# signal-board.net
KiCad netlist of a schematic drawn in EAGLE
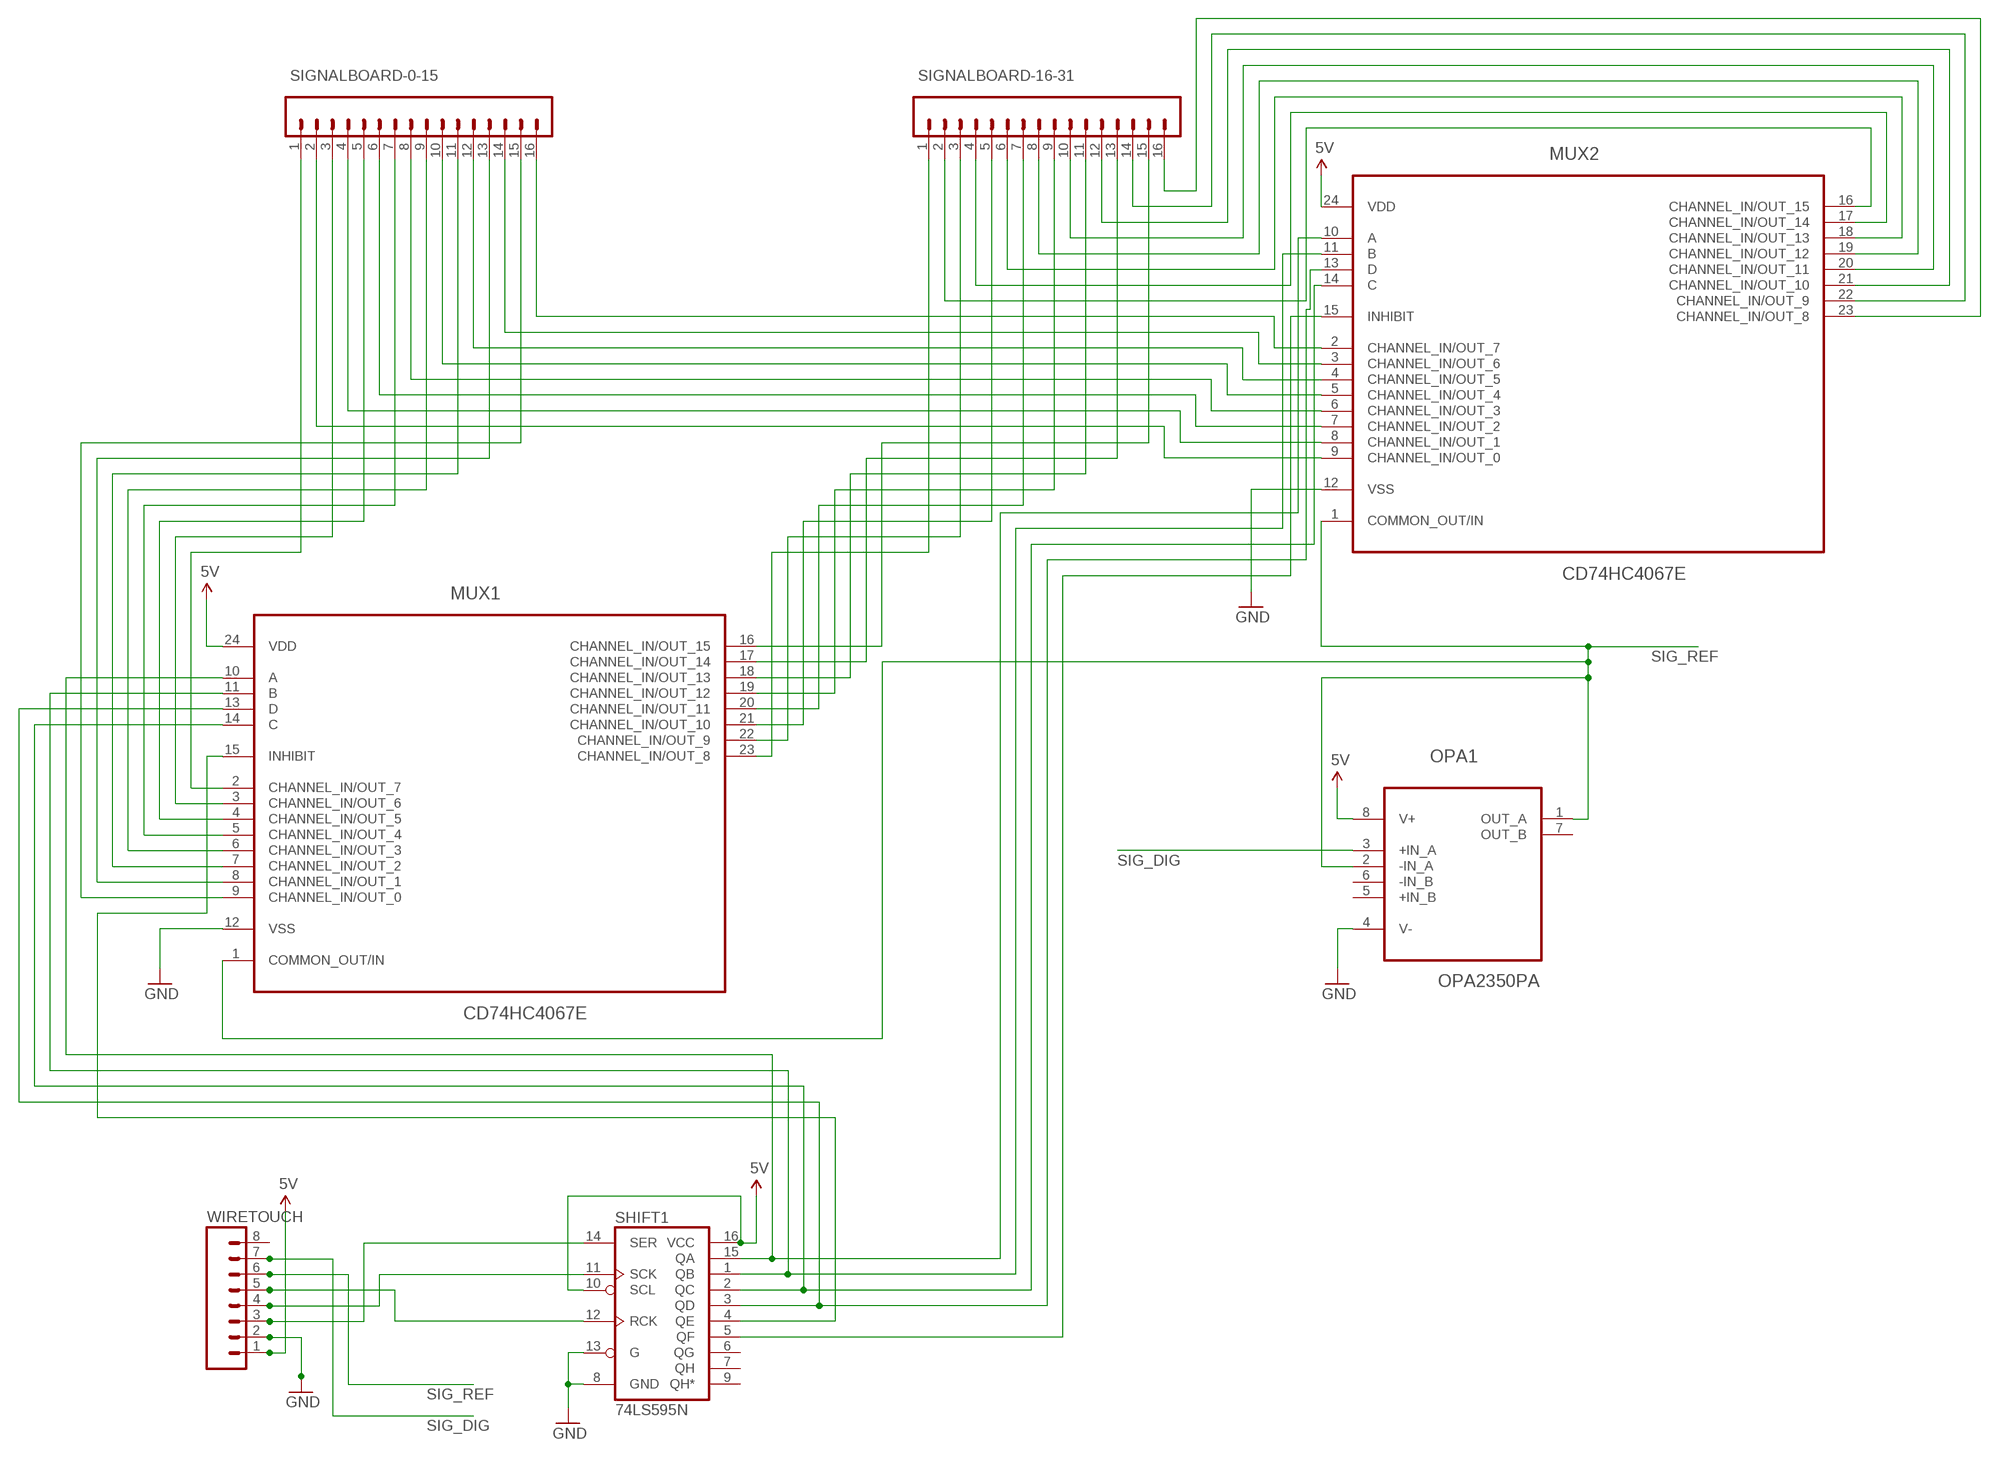
[diagram p0: schematic, sheet 1]

(export (version "E")
  (design (tool "Eeschema 10.0.6"))
  (components
    (comp (ref "MUX1")
      (value "CD74HC4067E")
      (footprint "eagle-import:PDIP24-WIDE-CD74HC4067E")
      (libsource (lib "eagle-import") (part "CD74HC4067E"))
    )
    (comp (ref "MUX2")
      (value "CD74HC4067E")
      (footprint "eagle-import:PDIP24-WIDE-CD74HC4067E")
      (libsource (lib "eagle-import") (part "CD74HC4067E"))
    )
    (comp (ref "OPA1")
      (value "OPA2350PA")
      (footprint "eagle-import:DIP254P762X508-8")
      (libsource (lib "eagle-import") (part "OPA2350PA"))
    )
    (comp (ref "SHIFT1")
      (value "74LS595N")
      (footprint "eagle-import:DIL16")
      (libsource (lib "eagle-import") (part "74595NLS"))
    )
    (comp (ref "SIGNALBOARD-0-15")
      (value "M16LOCK_LONGPADS")
      (footprint "eagle-import:1X16_LOCK_LONGPADS")
      (libsource (lib "eagle-import") (part "M16LOCK_LONGPADS"))
    )
    (comp (ref "SIGNALBOARD-16-31")
      (value "M16LOCK_LONGPADS")
      (footprint "eagle-import:1X16_LOCK_LONGPADS")
      (libsource (lib "eagle-import") (part "M16LOCK_LONGPADS"))
    )
    (comp (ref "WIRETOUCH")
      (value "M08LONGPADS")
      (footprint "eagle-import:1X08_LONGPADS")
      (libsource (lib "eagle-import") (part "M08LONGPADS"))
    )
  )
  (nets
    (net (code "1") (name "/SIG_DIG") (class "Default")
      (node (ref "OPA1") (pin "3") (pinfunction "+IN_A_3") (pintype "input"))
      (node (ref "WIRETOUCH") (pin "7") (pinfunction "7_7") (pintype "passive"))
    )
    (net (code "2") (name "/SIG_REF") (class "Default")
      (node (ref "MUX1") (pin "1") (pinfunction "COMMON_OUT/IN_1") (pintype "passive"))
      (node (ref "MUX2") (pin "1") (pinfunction "COMMON_OUT/IN_1") (pintype "passive"))
      (node (ref "OPA1") (pin "1") (pinfunction "OUT_A_1") (pintype "output"))
      (node (ref "OPA1") (pin "2") (pinfunction "-IN_A_2") (pintype "input"))
      (node (ref "WIRETOUCH") (pin "6") (pinfunction "6_6") (pintype "passive"))
    )
    (net (code "3") (name "5V") (class "Default")
      (node (ref "MUX1") (pin "24") (pinfunction "VDD_24") (pintype "power_in"))
      (node (ref "MUX2") (pin "24") (pinfunction "VDD_24") (pintype "power_in"))
      (node (ref "OPA1") (pin "8") (pinfunction "V+_8") (pintype "power_in"))
      (node (ref "SHIFT1") (pin "10") (pinfunction "SCL_10") (pintype "input"))
      (node (ref "SHIFT1") (pin "16") (pinfunction "VCC_16") (pintype "power_in"))
      (node (ref "WIRETOUCH") (pin "1") (pinfunction "1_1") (pintype "passive"))
    )
    (net (code "4") (name "GND") (class "Default")
      (node (ref "MUX1") (pin "12") (pinfunction "VSS_12") (pintype "power_in"))
      (node (ref "MUX2") (pin "12") (pinfunction "VSS_12") (pintype "power_in"))
      (node (ref "OPA1") (pin "4") (pinfunction "V-_4") (pintype "power_in"))
      (node (ref "SHIFT1") (pin "13") (pinfunction "G_13") (pintype "input"))
      (node (ref "SHIFT1") (pin "8") (pinfunction "GND_8") (pintype "power_in"))
      (node (ref "WIRETOUCH") (pin "2") (pinfunction "2_2") (pintype "passive"))
    )
    (net (code "5") (name "Net-(MUX1-A)") (class "Default")
      (node (ref "MUX1") (pin "10") (pinfunction "A_10") (pintype "input"))
      (node (ref "MUX2") (pin "10") (pinfunction "A_10") (pintype "input"))
      (node (ref "SHIFT1") (pin "15") (pinfunction "QA_15") (pintype "tri_state"))
    )
    (net (code "6") (name "Net-(MUX1-B)") (class "Default")
      (node (ref "MUX1") (pin "11") (pinfunction "B_11") (pintype "input"))
      (node (ref "MUX2") (pin "11") (pinfunction "B_11") (pintype "input"))
      (node (ref "SHIFT1") (pin "1") (pinfunction "QB_1") (pintype "tri_state"))
    )
    (net (code "7") (name "Net-(MUX1-C)") (class "Default")
      (node (ref "MUX1") (pin "14") (pinfunction "C_14") (pintype "input"))
      (node (ref "MUX2") (pin "14") (pinfunction "C_14") (pintype "input"))
      (node (ref "SHIFT1") (pin "2") (pinfunction "QC_2") (pintype "tri_state"))
    )
    (net (code "8") (name "Net-(MUX1-CHANNEL_IN{slash}OUT_0)") (class "Default")
      (node (ref "MUX1") (pin "9") (pinfunction "CHANNEL_IN/OUT_0_9") (pintype "bidirectional"))
      (node (ref "SIGNALBOARD-0-15") (pin "15") (pinfunction "15_15") (pintype "passive"))
    )
    (net (code "9") (name "Net-(MUX1-CHANNEL_IN{slash}OUT_1)") (class "Default")
      (node (ref "MUX1") (pin "8") (pinfunction "CHANNEL_IN/OUT_1_8") (pintype "bidirectional"))
      (node (ref "SIGNALBOARD-0-15") (pin "13") (pinfunction "13_13") (pintype "passive"))
    )
    (net (code "10") (name "Net-(MUX1-CHANNEL_IN{slash}OUT_2)") (class "Default")
      (node (ref "MUX1") (pin "7") (pinfunction "CHANNEL_IN/OUT_2_7") (pintype "bidirectional"))
      (node (ref "SIGNALBOARD-0-15") (pin "11") (pinfunction "11_11") (pintype "passive"))
    )
    (net (code "11") (name "Net-(MUX1-CHANNEL_IN{slash}OUT_3)") (class "Default")
      (node (ref "MUX1") (pin "6") (pinfunction "CHANNEL_IN/OUT_3_6") (pintype "bidirectional"))
      (node (ref "SIGNALBOARD-0-15") (pin "9") (pinfunction "9_9") (pintype "passive"))
    )
    (net (code "12") (name "Net-(MUX1-CHANNEL_IN{slash}OUT_4)") (class "Default")
      (node (ref "MUX1") (pin "5") (pinfunction "CHANNEL_IN/OUT_4_5") (pintype "bidirectional"))
      (node (ref "SIGNALBOARD-0-15") (pin "7") (pinfunction "7_7") (pintype "passive"))
    )
    (net (code "13") (name "Net-(MUX1-CHANNEL_IN{slash}OUT_5)") (class "Default")
      (node (ref "MUX1") (pin "4") (pinfunction "CHANNEL_IN/OUT_5_4") (pintype "bidirectional"))
      (node (ref "SIGNALBOARD-0-15") (pin "5") (pinfunction "5_5") (pintype "passive"))
    )
    (net (code "14") (name "Net-(MUX1-CHANNEL_IN{slash}OUT_6)") (class "Default")
      (node (ref "MUX1") (pin "3") (pinfunction "CHANNEL_IN/OUT_6_3") (pintype "bidirectional"))
      (node (ref "SIGNALBOARD-0-15") (pin "3") (pinfunction "3_3") (pintype "passive"))
    )
    (net (code "15") (name "Net-(MUX1-CHANNEL_IN{slash}OUT_7)") (class "Default")
      (node (ref "MUX1") (pin "2") (pinfunction "CHANNEL_IN/OUT_7_2") (pintype "bidirectional"))
      (node (ref "SIGNALBOARD-0-15") (pin "1") (pinfunction "1_1") (pintype "passive"))
    )
    (net (code "16") (name "Net-(MUX1-CHANNEL_IN{slash}OUT_8)") (class "Default")
      (node (ref "MUX1") (pin "23") (pinfunction "CHANNEL_IN/OUT_8_23") (pintype "bidirectional"))
      (node (ref "SIGNALBOARD-16-31") (pin "1") (pinfunction "1_1") (pintype "passive"))
    )
    (net (code "17") (name "Net-(MUX1-CHANNEL_IN{slash}OUT_9)") (class "Default")
      (node (ref "MUX1") (pin "22") (pinfunction "CHANNEL_IN/OUT_9_22") (pintype "bidirectional"))
      (node (ref "SIGNALBOARD-16-31") (pin "3") (pinfunction "3_3") (pintype "passive"))
    )
    (net (code "18") (name "Net-(MUX1-CHANNEL_IN{slash}OUT_10)") (class "Default")
      (node (ref "MUX1") (pin "21") (pinfunction "CHANNEL_IN/OUT_10_21") (pintype "bidirectional"))
      (node (ref "SIGNALBOARD-16-31") (pin "5") (pinfunction "5_5") (pintype "passive"))
    )
    (net (code "19") (name "Net-(MUX1-CHANNEL_IN{slash}OUT_11)") (class "Default")
      (node (ref "MUX1") (pin "20") (pinfunction "CHANNEL_IN/OUT_11_20") (pintype "bidirectional"))
      (node (ref "SIGNALBOARD-16-31") (pin "7") (pinfunction "7_7") (pintype "passive"))
    )
    (net (code "20") (name "Net-(MUX1-CHANNEL_IN{slash}OUT_12)") (class "Default")
      (node (ref "MUX1") (pin "19") (pinfunction "CHANNEL_IN/OUT_12_19") (pintype "bidirectional"))
      (node (ref "SIGNALBOARD-16-31") (pin "9") (pinfunction "9_9") (pintype "passive"))
    )
    (net (code "21") (name "Net-(MUX1-CHANNEL_IN{slash}OUT_13)") (class "Default")
      (node (ref "MUX1") (pin "18") (pinfunction "CHANNEL_IN/OUT_13_18") (pintype "bidirectional"))
      (node (ref "SIGNALBOARD-16-31") (pin "11") (pinfunction "11_11") (pintype "passive"))
    )
    (net (code "22") (name "Net-(MUX1-CHANNEL_IN{slash}OUT_14)") (class "Default")
      (node (ref "MUX1") (pin "17") (pinfunction "CHANNEL_IN/OUT_14_17") (pintype "bidirectional"))
      (node (ref "SIGNALBOARD-16-31") (pin "13") (pinfunction "13_13") (pintype "passive"))
    )
    (net (code "23") (name "Net-(MUX1-CHANNEL_IN{slash}OUT_15)") (class "Default")
      (node (ref "MUX1") (pin "16") (pinfunction "CHANNEL_IN/OUT_15_16") (pintype "bidirectional"))
      (node (ref "SIGNALBOARD-16-31") (pin "15") (pinfunction "15_15") (pintype "passive"))
    )
    (net (code "24") (name "Net-(MUX1-D)") (class "Default")
      (node (ref "MUX1") (pin "13") (pinfunction "D_13") (pintype "input"))
      (node (ref "MUX2") (pin "13") (pinfunction "D_13") (pintype "input"))
      (node (ref "SHIFT1") (pin "3") (pinfunction "QD_3") (pintype "tri_state"))
    )
    (net (code "25") (name "Net-(MUX1-INHIBIT)") (class "Default")
      (node (ref "MUX1") (pin "15") (pinfunction "INHIBIT_15") (pintype "input"))
      (node (ref "SHIFT1") (pin "4") (pinfunction "QE_4") (pintype "tri_state"))
    )
    (net (code "26") (name "Net-(MUX2-CHANNEL_IN{slash}OUT_0)") (class "Default")
      (node (ref "MUX2") (pin "9") (pinfunction "CHANNEL_IN/OUT_0_9") (pintype "bidirectional"))
      (node (ref "SIGNALBOARD-0-15") (pin "2") (pinfunction "2_2") (pintype "passive"))
    )
    (net (code "27") (name "Net-(MUX2-CHANNEL_IN{slash}OUT_1)") (class "Default")
      (node (ref "MUX2") (pin "8") (pinfunction "CHANNEL_IN/OUT_1_8") (pintype "bidirectional"))
      (node (ref "SIGNALBOARD-0-15") (pin "4") (pinfunction "4_4") (pintype "passive"))
    )
    (net (code "28") (name "Net-(MUX2-CHANNEL_IN{slash}OUT_2)") (class "Default")
      (node (ref "MUX2") (pin "7") (pinfunction "CHANNEL_IN/OUT_2_7") (pintype "bidirectional"))
      (node (ref "SIGNALBOARD-0-15") (pin "6") (pinfunction "6_6") (pintype "passive"))
    )
    (net (code "29") (name "Net-(MUX2-CHANNEL_IN{slash}OUT_3)") (class "Default")
      (node (ref "MUX2") (pin "6") (pinfunction "CHANNEL_IN/OUT_3_6") (pintype "bidirectional"))
      (node (ref "SIGNALBOARD-0-15") (pin "8") (pinfunction "8_8") (pintype "passive"))
    )
    (net (code "30") (name "Net-(MUX2-CHANNEL_IN{slash}OUT_4)") (class "Default")
      (node (ref "MUX2") (pin "5") (pinfunction "CHANNEL_IN/OUT_4_5") (pintype "bidirectional"))
      (node (ref "SIGNALBOARD-0-15") (pin "10") (pinfunction "10_10") (pintype "passive"))
    )
    (net (code "31") (name "Net-(MUX2-CHANNEL_IN{slash}OUT_5)") (class "Default")
      (node (ref "MUX2") (pin "4") (pinfunction "CHANNEL_IN/OUT_5_4") (pintype "bidirectional"))
      (node (ref "SIGNALBOARD-0-15") (pin "12") (pinfunction "12_12") (pintype "passive"))
    )
    (net (code "32") (name "Net-(MUX2-CHANNEL_IN{slash}OUT_6)") (class "Default")
      (node (ref "MUX2") (pin "3") (pinfunction "CHANNEL_IN/OUT_6_3") (pintype "bidirectional"))
      (node (ref "SIGNALBOARD-0-15") (pin "14") (pinfunction "14_14") (pintype "passive"))
    )
    (net (code "33") (name "Net-(MUX2-CHANNEL_IN{slash}OUT_7)") (class "Default")
      (node (ref "MUX2") (pin "2") (pinfunction "CHANNEL_IN/OUT_7_2") (pintype "bidirectional"))
      (node (ref "SIGNALBOARD-0-15") (pin "16") (pinfunction "16_16") (pintype "passive"))
    )
    (net (code "34") (name "Net-(MUX2-CHANNEL_IN{slash}OUT_8)") (class "Default")
      (node (ref "MUX2") (pin "23") (pinfunction "CHANNEL_IN/OUT_8_23") (pintype "bidirectional"))
      (node (ref "SIGNALBOARD-16-31") (pin "16") (pinfunction "16_16") (pintype "passive"))
    )
    (net (code "35") (name "Net-(MUX2-CHANNEL_IN{slash}OUT_9)") (class "Default")
      (node (ref "MUX2") (pin "22") (pinfunction "CHANNEL_IN/OUT_9_22") (pintype "bidirectional"))
      (node (ref "SIGNALBOARD-16-31") (pin "14") (pinfunction "14_14") (pintype "passive"))
    )
    (net (code "36") (name "Net-(MUX2-CHANNEL_IN{slash}OUT_10)") (class "Default")
      (node (ref "MUX2") (pin "21") (pinfunction "CHANNEL_IN/OUT_10_21") (pintype "bidirectional"))
      (node (ref "SIGNALBOARD-16-31") (pin "12") (pinfunction "12_12") (pintype "passive"))
    )
    (net (code "37") (name "Net-(MUX2-CHANNEL_IN{slash}OUT_11)") (class "Default")
      (node (ref "MUX2") (pin "20") (pinfunction "CHANNEL_IN/OUT_11_20") (pintype "bidirectional"))
      (node (ref "SIGNALBOARD-16-31") (pin "10") (pinfunction "10_10") (pintype "passive"))
    )
    (net (code "38") (name "Net-(MUX2-CHANNEL_IN{slash}OUT_12)") (class "Default")
      (node (ref "MUX2") (pin "19") (pinfunction "CHANNEL_IN/OUT_12_19") (pintype "bidirectional"))
      (node (ref "SIGNALBOARD-16-31") (pin "8") (pinfunction "8_8") (pintype "passive"))
    )
    (net (code "39") (name "Net-(MUX2-CHANNEL_IN{slash}OUT_13)") (class "Default")
      (node (ref "MUX2") (pin "18") (pinfunction "CHANNEL_IN/OUT_13_18") (pintype "bidirectional"))
      (node (ref "SIGNALBOARD-16-31") (pin "6") (pinfunction "6_6") (pintype "passive"))
    )
    (net (code "40") (name "Net-(MUX2-CHANNEL_IN{slash}OUT_14)") (class "Default")
      (node (ref "MUX2") (pin "17") (pinfunction "CHANNEL_IN/OUT_14_17") (pintype "bidirectional"))
      (node (ref "SIGNALBOARD-16-31") (pin "4") (pinfunction "4_4") (pintype "passive"))
    )
    (net (code "41") (name "Net-(MUX2-CHANNEL_IN{slash}OUT_15)") (class "Default")
      (node (ref "MUX2") (pin "16") (pinfunction "CHANNEL_IN/OUT_15_16") (pintype "bidirectional"))
      (node (ref "SIGNALBOARD-16-31") (pin "2") (pinfunction "2_2") (pintype "passive"))
    )
    (net (code "42") (name "Net-(MUX2-INHIBIT)") (class "Default")
      (node (ref "MUX2") (pin "15") (pinfunction "INHIBIT_15") (pintype "input"))
      (node (ref "SHIFT1") (pin "5") (pinfunction "QF_5") (pintype "tri_state"))
    )
    (net (code "43") (name "Net-(SHIFT1-RCK)") (class "Default")
      (node (ref "SHIFT1") (pin "12") (pinfunction "RCK_12") (pintype "input"))
      (node (ref "WIRETOUCH") (pin "5") (pinfunction "5_5") (pintype "passive"))
    )
    (net (code "44") (name "Net-(SHIFT1-SCK)") (class "Default")
      (node (ref "SHIFT1") (pin "11") (pinfunction "SCK_11") (pintype "input"))
      (node (ref "WIRETOUCH") (pin "4") (pinfunction "4_4") (pintype "passive"))
    )
    (net (code "45") (name "Net-(SHIFT1-SER)") (class "Default")
      (node (ref "SHIFT1") (pin "14") (pinfunction "SER_14") (pintype "input"))
      (node (ref "WIRETOUCH") (pin "3") (pinfunction "3_3") (pintype "passive"))
    )
    (net (code "46") (name "unconnected-(OPA1-+IN_B-Pad5)") (class "Default")
      (node (ref "OPA1") (pin "5") (pinfunction "+IN_B_5") (pintype "input"))
    )
    (net (code "47") (name "unconnected-(OPA1--IN_B-Pad6)") (class "Default")
      (node (ref "OPA1") (pin "6") (pinfunction "-IN_B_6") (pintype "input"))
    )
    (net (code "48") (name "unconnected-(OPA1-OUT_B-Pad7)") (class "Default")
      (node (ref "OPA1") (pin "7") (pinfunction "OUT_B_7") (pintype "output"))
    )
    (net (code "49") (name "unconnected-(SHIFT1-QG-Pad6)") (class "Default")
      (node (ref "SHIFT1") (pin "6") (pinfunction "QG_6") (pintype "tri_state"))
    )
    (net (code "50") (name "unconnected-(SHIFT1-QH*-Pad9)") (class "Default")
      (node (ref "SHIFT1") (pin "9") (pinfunction "QH*_9") (pintype "tri_state"))
    )
    (net (code "51") (name "unconnected-(SHIFT1-QH-Pad7)") (class "Default")
      (node (ref "SHIFT1") (pin "7") (pinfunction "QH_7") (pintype "tri_state"))
    )
    (net (code "52") (name "unconnected-(WIRETOUCH-Pad8)") (class "Default")
      (node (ref "WIRETOUCH") (pin "8") (pinfunction "8_8") (pintype "passive"))
    )
  )
)
